# mega_shield3.net
KiCad netlist of a schematic drawn in EAGLE
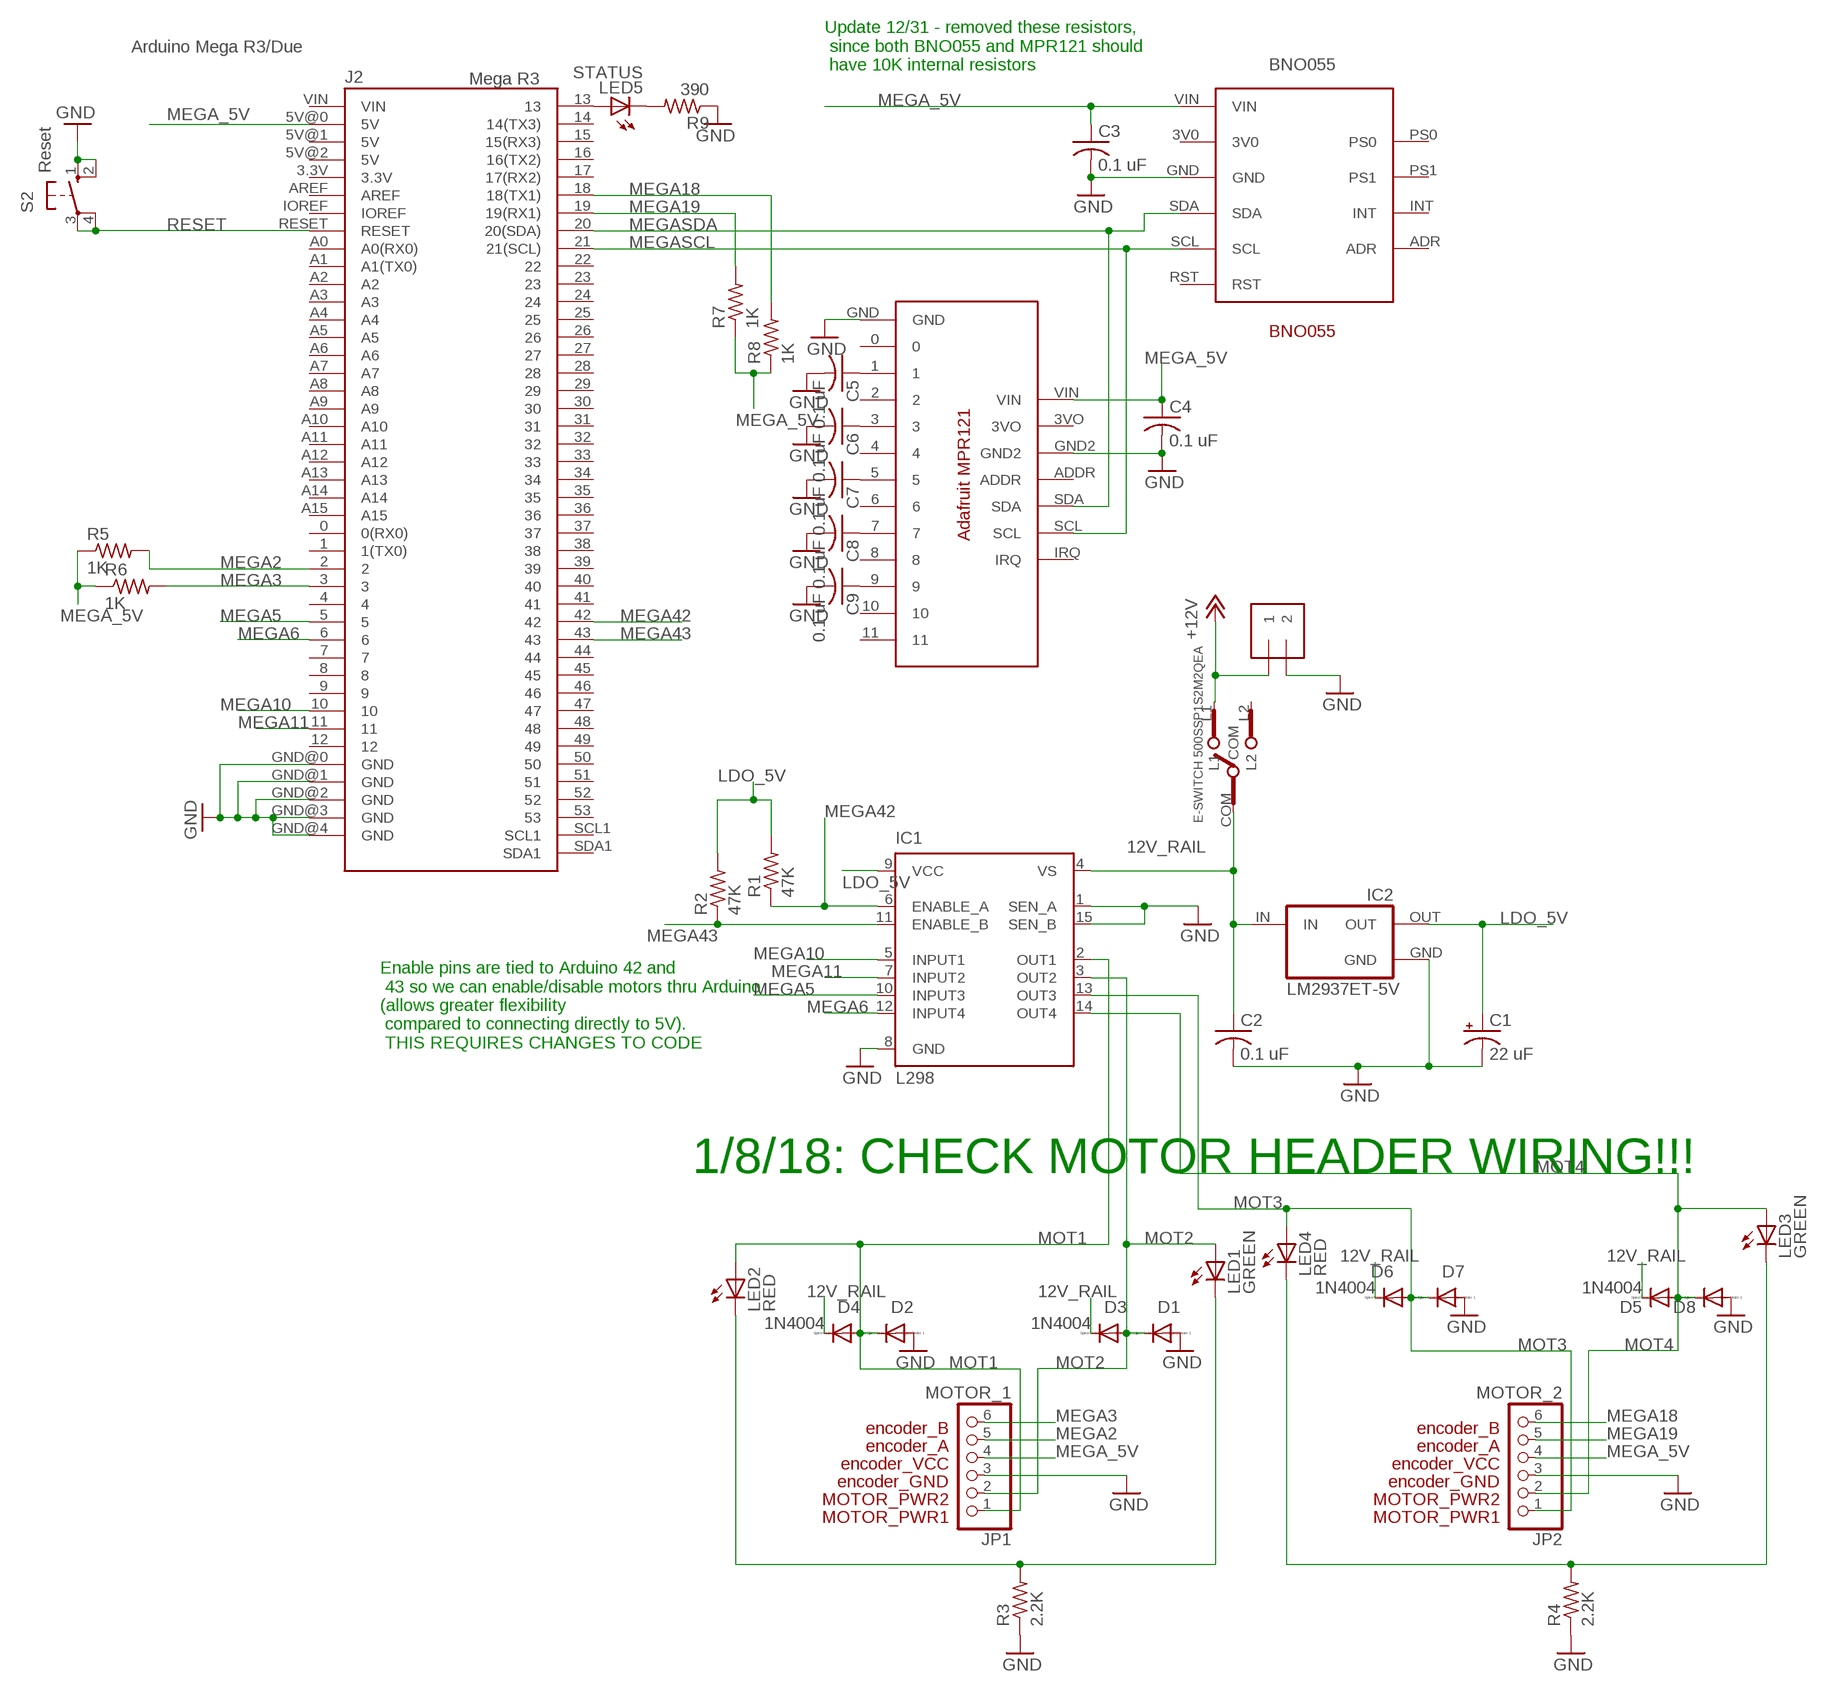
[diagram p0: schematic, sheet 1]

(export (version "E")
  (design (tool "Eeschema 10.0.6"))
  (components
    (comp (ref "12V_IN")
      (value "1X2-3.5MM")
      (footprint "eagle-import:1X2-3.5MM")
      (libsource (lib "eagle-import") (part "1X2-3.5MM"))
    )
    (comp (ref "BNO055")
      (value "BNO055")
      (footprint "eagle-import:BNO055")
      (libsource (lib "eagle-import") (part "BNO055"))
    )
    (comp (ref "C1")
      (value "22 uF")
      (footprint "eagle-import:B45181A")
      (libsource (lib "eagle-import") (part "CPOL-USB45181A"))
    )
    (comp (ref "C2")
      (value "0.1 uF")
      (footprint "eagle-import:C025-050X050")
      (libsource (lib "eagle-import") (part "C-US025-050X050"))
    )
    (comp (ref "C3")
      (value "0.1 uF")
      (footprint "eagle-import:C025-050X050")
      (libsource (lib "eagle-import") (part "C-US025-050X050"))
    )
    (comp (ref "C4")
      (value "0.1 uF")
      (footprint "eagle-import:C025-050X050")
      (libsource (lib "eagle-import") (part "C-US025-050X050"))
    )
    (comp (ref "C5")
      (value "0.1 uF")
      (footprint "eagle-import:C025-050X050")
      (libsource (lib "eagle-import") (part "C-US025-050X050"))
    )
    (comp (ref "C6")
      (value "0.1 uF")
      (footprint "eagle-import:C025-050X050")
      (libsource (lib "eagle-import") (part "C-US025-050X050"))
    )
    (comp (ref "C7")
      (value "0.1 uF")
      (footprint "eagle-import:C025-050X050")
      (libsource (lib "eagle-import") (part "C-US025-050X050"))
    )
    (comp (ref "C8")
      (value "0.1 uF")
      (footprint "eagle-import:C025-050X050")
      (libsource (lib "eagle-import") (part "C-US025-050X050"))
    )
    (comp (ref "C9")
      (value "0.1 uF")
      (footprint "eagle-import:C025-050X050")
      (libsource (lib "eagle-import") (part "C-US025-050X050"))
    )
    (comp (ref "D1")
      (value "1N4004")
      (footprint "eagle-import:DO41-10")
      (libsource (lib "eagle-import") (part "1N4004"))
    )
    (comp (ref "D2")
      (value "1N4004")
      (footprint "eagle-import:DO41-10")
      (libsource (lib "eagle-import") (part "1N4004"))
    )
    (comp (ref "D3")
      (value "1N4004")
      (footprint "eagle-import:DO41-10")
      (libsource (lib "eagle-import") (part "1N4004"))
    )
    (comp (ref "D4")
      (value "1N4004")
      (footprint "eagle-import:DO41-10")
      (libsource (lib "eagle-import") (part "1N4004"))
    )
    (comp (ref "D5")
      (value "1N4004")
      (footprint "eagle-import:DO41-10")
      (libsource (lib "eagle-import") (part "1N4004"))
    )
    (comp (ref "D6")
      (value "1N4004")
      (footprint "eagle-import:DO41-10")
      (libsource (lib "eagle-import") (part "1N4004"))
    )
    (comp (ref "D7")
      (value "1N4004")
      (footprint "eagle-import:DO41-10")
      (libsource (lib "eagle-import") (part "1N4004"))
    )
    (comp (ref "D8")
      (value "1N4004")
      (footprint "eagle-import:DO41-10")
      (libsource (lib "eagle-import") (part "1N4004"))
    )
    (comp (ref "IC1")
      (value "L298")
      (footprint "eagle-import:MULTIWATT-15")
      (fields (field (name "MPN") "L298N"))
      (libsource (lib "eagle-import") (part "L298"))
    )
    (comp (ref "IC2")
      (value "LM2937ET-5V")
      (footprint "eagle-import:TO220(V)")
      (libsource (lib "eagle-import") (part "LM2937ET-5,0"))
    )
    (comp (ref "J2")
      (value "Mega R3")
      (footprint "eagle-import:ARDUINO_MEGA")
      (libsource (lib "eagle-import") (part "ARDUINO-MEGAFULL"))
    )
    (comp (ref "JP1")
      (value "MOTOR_1")
      (footprint "eagle-import:1X06")
      (libsource (lib "eagle-import") (part "PINHD-1X6"))
    )
    (comp (ref "JP2")
      (value "MOTOR_2")
      (footprint "eagle-import:1X06")
      (libsource (lib "eagle-import") (part "PINHD-1X6"))
    )
    (comp (ref "LED1")
      (value "GREEN")
      (footprint "eagle-import:LED3MM")
      (libsource (lib "eagle-import") (part "LED3MM"))
    )
    (comp (ref "LED2")
      (value "RED")
      (footprint "eagle-import:LED3MM")
      (libsource (lib "eagle-import") (part "LED3MM"))
    )
    (comp (ref "LED3")
      (value "GREEN")
      (footprint "eagle-import:LED3MM")
      (libsource (lib "eagle-import") (part "LED3MM"))
    )
    (comp (ref "LED4")
      (value "RED")
      (footprint "eagle-import:LED3MM")
      (libsource (lib "eagle-import") (part "LED3MM"))
    )
    (comp (ref "LED5")
      (value "STATUS")
      (footprint "eagle-import:LED3MM")
      (libsource (lib "eagle-import") (part "LED3MM"))
    )
    (comp (ref "MPR121")
      (value "ADA_MPR121")
      (footprint "eagle-import:ADA_MPR121")
      (libsource (lib "eagle-import") (part "ADA_MPR121"))
    )
    (comp (ref "R1")
      (value "47K")
      (footprint "eagle-import:0207_10")
      (libsource (lib "eagle-import") (part "R-US_0207/10"))
    )
    (comp (ref "R2")
      (value "47K")
      (footprint "eagle-import:0207_10")
      (libsource (lib "eagle-import") (part "R-US_0207/10"))
    )
    (comp (ref "R3")
      (value "2.2K")
      (footprint "eagle-import:0207_10")
      (libsource (lib "eagle-import") (part "R-US_0207/10"))
    )
    (comp (ref "R4")
      (value "2.2K")
      (footprint "eagle-import:0207_10")
      (libsource (lib "eagle-import") (part "R-US_0207/10"))
    )
    (comp (ref "R5")
      (value "1K")
      (footprint "eagle-import:0207_10")
      (libsource (lib "eagle-import") (part "R-US_0207/10"))
    )
    (comp (ref "R6")
      (value "1K")
      (footprint "eagle-import:0207_10")
      (libsource (lib "eagle-import") (part "R-US_0207/10"))
    )
    (comp (ref "R7")
      (value "1K")
      (footprint "eagle-import:0207_10")
      (libsource (lib "eagle-import") (part "R-US_0207/10"))
    )
    (comp (ref "R8")
      (value "1K")
      (footprint "eagle-import:0207_10")
      (libsource (lib "eagle-import") (part "R-US_0207/10"))
    )
    (comp (ref "R9")
      (value "390")
      (footprint "eagle-import:0207_10")
      (libsource (lib "eagle-import") (part "R-US_0207/10"))
    )
    (comp (ref "S2")
      (value "Reset")
      (footprint "eagle-import:B3F-10XX")
      (fields (field (name "MPN") "B3F-1000"))
      (libsource (lib "eagle-import") (part "10-XX"))
    )
    (comp (ref "SLIDE_SW")
      (value "E-SWITCH_500SSP1S2M2QEA")
      (footprint "eagle-import:E-SWITCH_500SSP1S2M2QEA")
      (libsource (lib "eagle-import") (part "E-SWITCH_500SSP1S2M2QEA"))
    )
  )
  (nets
    (net (code "1") (name "+12V") (class "Default")
      (node (ref "12V_IN") (pin "1") (pinfunction "1_1") (pintype "passive"))
      (node (ref "SLIDE_SW") (pin "L1") (pinfunction "L1_L1") (pintype "bidirectional"))
    )
    (net (code "2") (name "/12V_RAIL") (class "Default")
      (node (ref "C2") (pin "1") (pinfunction "1_1") (pintype "passive"))
      (node (ref "D3") (pin "C") (pinfunction "C_C") (pintype "passive"))
      (node (ref "D4") (pin "C") (pinfunction "C_C") (pintype "passive"))
      (node (ref "D5") (pin "C") (pinfunction "C_C") (pintype "passive"))
      (node (ref "D6") (pin "C") (pinfunction "C_C") (pintype "passive"))
      (node (ref "IC1") (pin "4") (pinfunction "VS_4") (pintype "power_in"))
      (node (ref "IC2") (pin "IN") (pinfunction "IN_IN") (pintype "input"))
      (node (ref "SLIDE_SW") (pin "COM") (pinfunction "COM_COM") (pintype "bidirectional"))
    )
    (net (code "3") (name "/LDO_5V") (class "Default")
      (node (ref "C1") (pin "+") (pinfunction "+_+") (pintype "passive"))
      (node (ref "IC1") (pin "9") (pinfunction "VCC_9") (pintype "power_in"))
      (node (ref "IC2") (pin "OUT") (pinfunction "OUT_OUT") (pintype "output"))
      (node (ref "R1") (pin "2") (pinfunction "2_2") (pintype "passive"))
      (node (ref "R2") (pin "2") (pinfunction "2_2") (pintype "passive"))
    )
    (net (code "4") (name "/MEGA2") (class "Default")
      (node (ref "J2") (pin "2") (pinfunction "2_2") (pintype "bidirectional"))
      (node (ref "JP1") (pin "5") (pinfunction "5_5") (pintype "passive"))
      (node (ref "R5") (pin "2") (pinfunction "2_2") (pintype "passive"))
    )
    (net (code "5") (name "/MEGA3") (class "Default")
      (node (ref "J2") (pin "3") (pinfunction "3_3") (pintype "bidirectional"))
      (node (ref "JP1") (pin "6") (pinfunction "6_6") (pintype "passive"))
      (node (ref "R6") (pin "2") (pinfunction "2_2") (pintype "passive"))
    )
    (net (code "6") (name "/MEGA5") (class "Default")
      (node (ref "IC1") (pin "10") (pinfunction "INPUT3_10") (pintype "input"))
      (node (ref "J2") (pin "5") (pinfunction "5_5") (pintype "bidirectional"))
    )
    (net (code "7") (name "/MEGA6") (class "Default")
      (node (ref "IC1") (pin "12") (pinfunction "INPUT4_12") (pintype "input"))
      (node (ref "J2") (pin "6") (pinfunction "6_6") (pintype "bidirectional"))
    )
    (net (code "8") (name "/MEGA10") (class "Default")
      (node (ref "IC1") (pin "5") (pinfunction "INPUT1_5") (pintype "input"))
      (node (ref "J2") (pin "10") (pinfunction "10_10") (pintype "bidirectional"))
    )
    (net (code "9") (name "/MEGA11") (class "Default")
      (node (ref "IC1") (pin "7") (pinfunction "INPUT2_7") (pintype "input"))
      (node (ref "J2") (pin "11") (pinfunction "11_11") (pintype "bidirectional"))
    )
    (net (code "10") (name "/MEGA18") (class "Default")
      (node (ref "J2") (pin "18") (pinfunction "18(TX1)_18") (pintype "bidirectional"))
      (node (ref "JP2") (pin "6") (pinfunction "6_6") (pintype "passive"))
      (node (ref "R8") (pin "2") (pinfunction "2_2") (pintype "passive"))
    )
    (net (code "11") (name "/MEGA19") (class "Default")
      (node (ref "J2") (pin "19") (pinfunction "19(RX1)_19") (pintype "bidirectional"))
      (node (ref "JP2") (pin "5") (pinfunction "5_5") (pintype "passive"))
      (node (ref "R7") (pin "2") (pinfunction "2_2") (pintype "passive"))
    )
    (net (code "12") (name "/MEGA42") (class "Default")
      (node (ref "IC1") (pin "6") (pinfunction "ENABLE_A_6") (pintype "input"))
      (node (ref "J2") (pin "42") (pinfunction "42_42") (pintype "bidirectional"))
      (node (ref "R1") (pin "1") (pinfunction "1_1") (pintype "passive"))
    )
    (net (code "13") (name "/MEGA43") (class "Default")
      (node (ref "IC1") (pin "11") (pinfunction "ENABLE_B_11") (pintype "input"))
      (node (ref "J2") (pin "43") (pinfunction "43_43") (pintype "bidirectional"))
      (node (ref "R2") (pin "1") (pinfunction "1_1") (pintype "passive"))
    )
    (net (code "14") (name "/MEGASCL") (class "Default")
      (node (ref "BNO055") (pin "SCL") (pinfunction "SCL_SCL") (pintype "bidirectional"))
      (node (ref "J2") (pin "21") (pinfunction "21(SCL)_21") (pintype "bidirectional"))
      (node (ref "MPR121") (pin "SCL") (pinfunction "SCL_SCL") (pintype "bidirectional"))
    )
    (net (code "15") (name "/MEGASDA") (class "Default")
      (node (ref "BNO055") (pin "SDA") (pinfunction "SDA_SDA") (pintype "bidirectional"))
      (node (ref "J2") (pin "20") (pinfunction "20(SDA)_20") (pintype "bidirectional"))
      (node (ref "MPR121") (pin "SDA") (pinfunction "SDA_SDA") (pintype "bidirectional"))
    )
    (net (code "16") (name "/MEGA_5V") (class "Default")
      (node (ref "BNO055") (pin "VIN") (pinfunction "VIN_VIN") (pintype "bidirectional"))
      (node (ref "C3") (pin "1") (pinfunction "1_1") (pintype "passive"))
      (node (ref "C4") (pin "1") (pinfunction "1_1") (pintype "passive"))
      (node (ref "J2") (pin "5V@0") (pinfunction "5V_5V@0") (pintype "bidirectional"))
      (node (ref "JP1") (pin "4") (pinfunction "4_4") (pintype "passive"))
      (node (ref "JP2") (pin "4") (pinfunction "4_4") (pintype "passive"))
      (node (ref "MPR121") (pin "VIN") (pinfunction "VIN_VIN") (pintype "bidirectional"))
      (node (ref "R5") (pin "1") (pinfunction "1_1") (pintype "passive"))
      (node (ref "R6") (pin "1") (pinfunction "1_1") (pintype "passive"))
      (node (ref "R7") (pin "1") (pinfunction "1_1") (pintype "passive"))
      (node (ref "R8") (pin "1") (pinfunction "1_1") (pintype "passive"))
    )
    (net (code "17") (name "/MOT1") (class "Default")
      (node (ref "D2") (pin "C") (pinfunction "C_C") (pintype "passive"))
      (node (ref "D4") (pin "A") (pinfunction "A_A") (pintype "passive"))
      (node (ref "IC1") (pin "2") (pinfunction "OUT1_2") (pintype "output"))
      (node (ref "JP1") (pin "1") (pinfunction "1_1") (pintype "passive"))
      (node (ref "LED2") (pin "A") (pinfunction "A_A") (pintype "passive"))
    )
    (net (code "18") (name "/MOT2") (class "Default")
      (node (ref "D1") (pin "C") (pinfunction "C_C") (pintype "passive"))
      (node (ref "D3") (pin "A") (pinfunction "A_A") (pintype "passive"))
      (node (ref "IC1") (pin "3") (pinfunction "OUT2_3") (pintype "output"))
      (node (ref "JP1") (pin "2") (pinfunction "2_2") (pintype "passive"))
      (node (ref "LED1") (pin "A") (pinfunction "A_A") (pintype "passive"))
    )
    (net (code "19") (name "/MOT3") (class "Default")
      (node (ref "D6") (pin "A") (pinfunction "A_A") (pintype "passive"))
      (node (ref "D7") (pin "C") (pinfunction "C_C") (pintype "passive"))
      (node (ref "IC1") (pin "13") (pinfunction "OUT3_13") (pintype "output"))
      (node (ref "JP2") (pin "1") (pinfunction "1_1") (pintype "passive"))
      (node (ref "LED4") (pin "A") (pinfunction "A_A") (pintype "passive"))
    )
    (net (code "20") (name "/MOT4") (class "Default")
      (node (ref "D5") (pin "A") (pinfunction "A_A") (pintype "passive"))
      (node (ref "D8") (pin "C") (pinfunction "C_C") (pintype "passive"))
      (node (ref "IC1") (pin "14") (pinfunction "OUT4_14") (pintype "output"))
      (node (ref "JP2") (pin "2") (pinfunction "2_2") (pintype "passive"))
      (node (ref "LED3") (pin "A") (pinfunction "A_A") (pintype "passive"))
    )
    (net (code "21") (name "/RESET") (class "Default")
      (node (ref "J2") (pin "RESET") (pinfunction "RESET_RESET") (pintype "bidirectional"))
      (node (ref "S2") (pin "3") (pinfunction "P_3") (pintype "passive"))
      (node (ref "S2") (pin "4") (pinfunction "P1_4") (pintype "passive"))
    )
    (net (code "22") (name "GND") (class "Default")
      (node (ref "12V_IN") (pin "2") (pinfunction "2_2") (pintype "passive"))
      (node (ref "BNO055") (pin "GND") (pinfunction "GND_GND") (pintype "bidirectional"))
      (node (ref "C1") (pin "-") (pinfunction "-_-") (pintype "passive"))
      (node (ref "C2") (pin "2") (pinfunction "2_2") (pintype "passive"))
      (node (ref "C3") (pin "2") (pinfunction "2_2") (pintype "passive"))
      (node (ref "C4") (pin "2") (pinfunction "2_2") (pintype "passive"))
      (node (ref "C5") (pin "2") (pinfunction "2_2") (pintype "passive"))
      (node (ref "C6") (pin "2") (pinfunction "2_2") (pintype "passive"))
      (node (ref "C7") (pin "2") (pinfunction "2_2") (pintype "passive"))
      (node (ref "C8") (pin "2") (pinfunction "2_2") (pintype "passive"))
      (node (ref "C9") (pin "2") (pinfunction "2_2") (pintype "passive"))
      (node (ref "D1") (pin "A") (pinfunction "A_A") (pintype "passive"))
      (node (ref "D2") (pin "A") (pinfunction "A_A") (pintype "passive"))
      (node (ref "D7") (pin "A") (pinfunction "A_A") (pintype "passive"))
      (node (ref "D8") (pin "A") (pinfunction "A_A") (pintype "passive"))
      (node (ref "IC1") (pin "1") (pinfunction "SEN_A_1") (pintype "input"))
      (node (ref "IC1") (pin "15") (pinfunction "SEN_B_15") (pintype "input"))
      (node (ref "IC1") (pin "8") (pinfunction "GND_8") (pintype "power_in"))
      (node (ref "IC2") (pin "GND") (pinfunction "GND_GND") (pintype "power_in"))
      (node (ref "J2") (pin "GND@0") (pinfunction "GND_GND@0") (pintype "bidirectional"))
      (node (ref "J2") (pin "GND@1") (pinfunction "GND_GND@1") (pintype "bidirectional"))
      (node (ref "J2") (pin "GND@2") (pinfunction "GND_GND@2") (pintype "bidirectional"))
      (node (ref "J2") (pin "GND@3") (pinfunction "GND_GND@3") (pintype "bidirectional"))
      (node (ref "J2") (pin "GND@4") (pinfunction "GND_GND@4") (pintype "bidirectional"))
      (node (ref "JP1") (pin "3") (pinfunction "3_3") (pintype "passive"))
      (node (ref "JP2") (pin "3") (pinfunction "3_3") (pintype "passive"))
      (node (ref "MPR121") (pin "GND") (pinfunction "GND_GND") (pintype "bidirectional"))
      (node (ref "MPR121") (pin "GND2") (pinfunction "GND2_GND2") (pintype "bidirectional"))
      (node (ref "R3") (pin "1") (pinfunction "1_1") (pintype "passive"))
      (node (ref "R4") (pin "1") (pinfunction "1_1") (pintype "passive"))
      (node (ref "R9") (pin "1") (pinfunction "1_1") (pintype "passive"))
      (node (ref "S2") (pin "1") (pinfunction "S_1") (pintype "passive"))
      (node (ref "S2") (pin "2") (pinfunction "S1_2") (pintype "passive"))
    )
    (net (code "23") (name "Net-(C5-Pad1)") (class "Default")
      (node (ref "C5") (pin "1") (pinfunction "1_1") (pintype "passive"))
      (node (ref "MPR121") (pin "1") (pinfunction "1_1") (pintype "bidirectional"))
    )
    (net (code "24") (name "Net-(C6-Pad1)") (class "Default")
      (node (ref "C6") (pin "1") (pinfunction "1_1") (pintype "passive"))
      (node (ref "MPR121") (pin "3") (pinfunction "3_3") (pintype "bidirectional"))
    )
    (net (code "25") (name "Net-(C7-Pad1)") (class "Default")
      (node (ref "C7") (pin "1") (pinfunction "1_1") (pintype "passive"))
      (node (ref "MPR121") (pin "5") (pinfunction "5_5") (pintype "bidirectional"))
    )
    (net (code "26") (name "Net-(C8-Pad1)") (class "Default")
      (node (ref "C8") (pin "1") (pinfunction "1_1") (pintype "passive"))
      (node (ref "MPR121") (pin "7") (pinfunction "7_7") (pintype "bidirectional"))
    )
    (net (code "27") (name "Net-(C9-Pad1)") (class "Default")
      (node (ref "C9") (pin "1") (pinfunction "1_1") (pintype "passive"))
      (node (ref "MPR121") (pin "9") (pinfunction "9_9") (pintype "bidirectional"))
    )
    (net (code "28") (name "Net-(J2-Pad13)") (class "Default")
      (node (ref "J2") (pin "13") (pinfunction "13_13") (pintype "bidirectional"))
      (node (ref "LED5") (pin "A") (pinfunction "A_A") (pintype "passive"))
    )
    (net (code "29") (name "Net-(LED1-C)") (class "Default")
      (node (ref "LED1") (pin "K") (pinfunction "C_K") (pintype "passive"))
      (node (ref "LED2") (pin "K") (pinfunction "C_K") (pintype "passive"))
      (node (ref "R3") (pin "2") (pinfunction "2_2") (pintype "passive"))
    )
    (net (code "30") (name "Net-(LED3-C)") (class "Default")
      (node (ref "LED3") (pin "K") (pinfunction "C_K") (pintype "passive"))
      (node (ref "LED4") (pin "K") (pinfunction "C_K") (pintype "passive"))
      (node (ref "R4") (pin "2") (pinfunction "2_2") (pintype "passive"))
    )
    (net (code "31") (name "Net-(LED5-C)") (class "Default")
      (node (ref "LED5") (pin "K") (pinfunction "C_K") (pintype "passive"))
      (node (ref "R9") (pin "2") (pinfunction "2_2") (pintype "passive"))
    )
    (net (code "32") (name "unconnected-(BNO055-Pad3V0)") (class "Default")
      (node (ref "BNO055") (pin "3V0") (pinfunction "3V0_3V0") (pintype "bidirectional"))
    )
    (net (code "33") (name "unconnected-(BNO055-PadADR)") (class "Default")
      (node (ref "BNO055") (pin "ADR") (pinfunction "ADR_ADR") (pintype "bidirectional"))
    )
    (net (code "34") (name "unconnected-(BNO055-PadINT)") (class "Default")
      (node (ref "BNO055") (pin "INT") (pinfunction "INT_INT") (pintype "bidirectional"))
    )
    (net (code "35") (name "unconnected-(BNO055-PadPS0)") (class "Default")
      (node (ref "BNO055") (pin "PS0") (pinfunction "PS0_PS0") (pintype "bidirectional"))
    )
    (net (code "36") (name "unconnected-(BNO055-PadPS1)") (class "Default")
      (node (ref "BNO055") (pin "PS1") (pinfunction "PS1_PS1") (pintype "bidirectional"))
    )
    (net (code "37") (name "unconnected-(BNO055-PadRST)") (class "Default")
      (node (ref "BNO055") (pin "RST") (pinfunction "RST_RST") (pintype "bidirectional"))
    )
    (net (code "38") (name "unconnected-(J2-0(RX0)-Pad0)") (class "Default")
      (node (ref "J2") (pin "0") (pinfunction "0(RX0)_0") (pintype "bidirectional"))
    )
    (net (code "39") (name "unconnected-(J2-1(TX0)-Pad1)") (class "Default")
      (node (ref "J2") (pin "1") (pinfunction "1(TX0)_1") (pintype "bidirectional"))
    )
    (net (code "40") (name "unconnected-(J2-5V-Pad5V@1)") (class "Default")
      (node (ref "J2") (pin "5V@1") (pinfunction "5V_5V@1") (pintype "bidirectional"))
    )
    (net (code "41") (name "unconnected-(J2-5V-Pad5V@2)") (class "Default")
      (node (ref "J2") (pin "5V@2") (pinfunction "5V_5V@2") (pintype "bidirectional"))
    )
    (net (code "42") (name "unconnected-(J2-14(TX3)-Pad14)") (class "Default")
      (node (ref "J2") (pin "14") (pinfunction "14(TX3)_14") (pintype "bidirectional"))
    )
    (net (code "43") (name "unconnected-(J2-15(RX3)-Pad15)") (class "Default")
      (node (ref "J2") (pin "15") (pinfunction "15(RX3)_15") (pintype "bidirectional"))
    )
    (net (code "44") (name "unconnected-(J2-16(TX2)-Pad16)") (class "Default")
      (node (ref "J2") (pin "16") (pinfunction "16(TX2)_16") (pintype "bidirectional"))
    )
    (net (code "45") (name "unconnected-(J2-17(RX2)-Pad17)") (class "Default")
      (node (ref "J2") (pin "17") (pinfunction "17(RX2)_17") (pintype "bidirectional"))
    )
    (net (code "46") (name "unconnected-(J2-A0(RX0)-PadA0)") (class "Default")
      (node (ref "J2") (pin "A0") (pinfunction "A0(RX0)_A0") (pintype "bidirectional"))
    )
    (net (code "47") (name "unconnected-(J2-A1(TX0)-PadA1)") (class "Default")
      (node (ref "J2") (pin "A1") (pinfunction "A1(TX0)_A1") (pintype "bidirectional"))
    )
    (net (code "48") (name "unconnected-(J2-Pad3.3V)") (class "Default")
      (node (ref "J2") (pin "3.3V") (pinfunction "3.3V_3.3V") (pintype "bidirectional"))
    )
    (net (code "49") (name "unconnected-(J2-Pad4)") (class "Default")
      (node (ref "J2") (pin "4") (pinfunction "4_4") (pintype "bidirectional"))
    )
    (net (code "50") (name "unconnected-(J2-Pad7)") (class "Default")
      (node (ref "J2") (pin "7") (pinfunction "7_7") (pintype "bidirectional"))
    )
    (net (code "51") (name "unconnected-(J2-Pad8)") (class "Default")
      (node (ref "J2") (pin "8") (pinfunction "8_8") (pintype "bidirectional"))
    )
    (net (code "52") (name "unconnected-(J2-Pad9)") (class "Default")
      (node (ref "J2") (pin "9") (pinfunction "9_9") (pintype "bidirectional"))
    )
    (net (code "53") (name "unconnected-(J2-Pad12)") (class "Default")
      (node (ref "J2") (pin "12") (pinfunction "12_12") (pintype "bidirectional"))
    )
    (net (code "54") (name "unconnected-(J2-Pad22)") (class "Default")
      (node (ref "J2") (pin "22") (pinfunction "22_22") (pintype "bidirectional"))
    )
    (net (code "55") (name "unconnected-(J2-Pad23)") (class "Default")
      (node (ref "J2") (pin "23") (pinfunction "23_23") (pintype "bidirectional"))
    )
    (net (code "56") (name "unconnected-(J2-Pad24)") (class "Default")
      (node (ref "J2") (pin "24") (pinfunction "24_24") (pintype "bidirectional"))
    )
    (net (code "57") (name "unconnected-(J2-Pad25)") (class "Default")
      (node (ref "J2") (pin "25") (pinfunction "25_25") (pintype "bidirectional"))
    )
    (net (code "58") (name "unconnected-(J2-Pad26)") (class "Default")
      (node (ref "J2") (pin "26") (pinfunction "26_26") (pintype "bidirectional"))
    )
    (net (code "59") (name "unconnected-(J2-Pad27)") (class "Default")
      (node (ref "J2") (pin "27") (pinfunction "27_27") (pintype "bidirectional"))
    )
    (net (code "60") (name "unconnected-(J2-Pad28)") (class "Default")
      (node (ref "J2") (pin "28") (pinfunction "28_28") (pintype "bidirectional"))
    )
    (net (code "61") (name "unconnected-(J2-Pad29)") (class "Default")
      (node (ref "J2") (pin "29") (pinfunction "29_29") (pintype "bidirectional"))
    )
    (net (code "62") (name "unconnected-(J2-Pad30)") (class "Default")
      (node (ref "J2") (pin "30") (pinfunction "30_30") (pintype "bidirectional"))
    )
    (net (code "63") (name "unconnected-(J2-Pad31)") (class "Default")
      (node (ref "J2") (pin "31") (pinfunction "31_31") (pintype "bidirectional"))
    )
    (net (code "64") (name "unconnected-(J2-Pad32)") (class "Default")
      (node (ref "J2") (pin "32") (pinfunction "32_32") (pintype "bidirectional"))
    )
    (net (code "65") (name "unconnected-(J2-Pad33)") (class "Default")
      (node (ref "J2") (pin "33") (pinfunction "33_33") (pintype "bidirectional"))
    )
    (net (code "66") (name "unconnected-(J2-Pad34)") (class "Default")
      (node (ref "J2") (pin "34") (pinfunction "34_34") (pintype "bidirectional"))
    )
    (net (code "67") (name "unconnected-(J2-Pad35)") (class "Default")
      (node (ref "J2") (pin "35") (pinfunction "35_35") (pintype "bidirectional"))
    )
    (net (code "68") (name "unconnected-(J2-Pad36)") (class "Default")
      (node (ref "J2") (pin "36") (pinfunction "36_36") (pintype "bidirectional"))
    )
    (net (code "69") (name "unconnected-(J2-Pad37)") (class "Default")
      (node (ref "J2") (pin "37") (pinfunction "37_37") (pintype "bidirectional"))
    )
    (net (code "70") (name "unconnected-(J2-Pad38)") (class "Default")
      (node (ref "J2") (pin "38") (pinfunction "38_38") (pintype "bidirectional"))
    )
    (net (code "71") (name "unconnected-(J2-Pad39)") (class "Default")
      (node (ref "J2") (pin "39") (pinfunction "39_39") (pintype "bidirectional"))
    )
    (net (code "72") (name "unconnected-(J2-Pad40)") (class "Default")
      (node (ref "J2") (pin "40") (pinfunction "40_40") (pintype "bidirectional"))
    )
    (net (code "73") (name "unconnected-(J2-Pad41)") (class "Default")
      (node (ref "J2") (pin "41") (pinfunction "41_41") (pintype "bidirectional"))
    )
    (net (code "74") (name "unconnected-(J2-Pad44)") (class "Default")
      (node (ref "J2") (pin "44") (pinfunction "44_44") (pintype "bidirectional"))
    )
    (net (code "75") (name "unconnected-(J2-Pad45)") (class "Default")
      (node (ref "J2") (pin "45") (pinfunction "45_45") (pintype "bidirectional"))
    )
    (net (code "76") (name "unconnected-(J2-Pad46)") (class "Default")
      (node (ref "J2") (pin "46") (pinfunction "46_46") (pintype "bidirectional"))
    )
    (net (code "77") (name "unconnected-(J2-Pad47)") (class "Default")
      (node (ref "J2") (pin "47") (pinfunction "47_47") (pintype "bidirectional"))
    )
    (net (code "78") (name "unconnected-(J2-Pad48)") (class "Default")
      (node (ref "J2") (pin "48") (pinfunction "48_48") (pintype "bidirectional"))
    )
    (net (code "79") (name "unconnected-(J2-Pad49)") (class "Default")
      (node (ref "J2") (pin "49") (pinfunction "49_49") (pintype "bidirectional"))
    )
    (net (code "80") (name "unconnected-(J2-Pad50)") (class "Default")
      (node (ref "J2") (pin "50") (pinfunction "50_50") (pintype "bidirectional"))
    )
    (net (code "81") (name "unconnected-(J2-Pad51)") (class "Default")
      (node (ref "J2") (pin "51") (pinfunction "51_51") (pintype "bidirectional"))
    )
    (net (code "82") (name "unconnected-(J2-Pad52)") (class "Default")
      (node (ref "J2") (pin "52") (pinfunction "52_52") (pintype "bidirectional"))
    )
    (net (code "83") (name "unconnected-(J2-Pad53)") (class "Default")
      (node (ref "J2") (pin "53") (pinfunction "53_53") (pintype "bidirectional"))
    )
    (net (code "84") (name "unconnected-(J2-PadA2)") (class "Default")
      (node (ref "J2") (pin "A2") (pinfunction "A2_A2") (pintype "bidirectional"))
    )
    (net (code "85") (name "unconnected-(J2-PadA3)") (class "Default")
      (node (ref "J2") (pin "A3") (pinfunction "A3_A3") (pintype "bidirectional"))
    )
    (net (code "86") (name "unconnected-(J2-PadA4)") (class "Default")
      (node (ref "J2") (pin "A4") (pinfunction "A4_A4") (pintype "bidirectional"))
    )
    (net (code "87") (name "unconnected-(J2-PadA5)") (class "Default")
      (node (ref "J2") (pin "A5") (pinfunction "A5_A5") (pintype "bidirectional"))
    )
    (net (code "88") (name "unconnected-(J2-PadA6)") (class "Default")
      (node (ref "J2") (pin "A6") (pinfunction "A6_A6") (pintype "bidirectional"))
    )
    (net (code "89") (name "unconnected-(J2-PadA7)") (class "Default")
      (node (ref "J2") (pin "A7") (pinfunction "A7_A7") (pintype "bidirectional"))
    )
    (net (code "90") (name "unconnected-(J2-PadA8)") (class "Default")
      (node (ref "J2") (pin "A8") (pinfunction "A8_A8") (pintype "bidirectional"))
    )
    (net (code "91") (name "unconnected-(J2-PadA9)") (class "Default")
      (node (ref "J2") (pin "A9") (pinfunction "A9_A9") (pintype "bidirectional"))
    )
    (net (code "92") (name "unconnected-(J2-PadA10)") (class "Default")
      (node (ref "J2") (pin "A10") (pinfunction "A10_A10") (pintype "bidirectional"))
    )
    (net (code "93") (name "unconnected-(J2-PadA11)") (class "Default")
      (node (ref "J2") (pin "A11") (pinfunction "A11_A11") (pintype "bidirectional"))
    )
    (net (code "94") (name "unconnected-(J2-PadA12)") (class "Default")
      (node (ref "J2") (pin "A12") (pinfunction "A12_A12") (pintype "bidirectional"))
    )
    (net (code "95") (name "unconnected-(J2-PadA13)") (class "Default")
      (node (ref "J2") (pin "A13") (pinfunction "A13_A13") (pintype "bidirectional"))
    )
    (net (code "96") (name "unconnected-(J2-PadA14)") (class "Default")
      (node (ref "J2") (pin "A14") (pinfunction "A14_A14") (pintype "bidirectional"))
    )
    (net (code "97") (name "unconnected-(J2-PadA15)") (class "Default")
      (node (ref "J2") (pin "A15") (pinfunction "A15_A15") (pintype "bidirectional"))
    )
    (net (code "98") (name "unconnected-(J2-PadAREF)") (class "Default")
      (node (ref "J2") (pin "AREF") (pinfunction "AREF_AREF") (pintype "bidirectional"))
    )
    (net (code "99") (name "unconnected-(J2-PadIOREF)") (class "Default")
      (node (ref "J2") (pin "IOREF") (pinfunction "IOREF_IOREF") (pintype "bidirectional"))
    )
    (net (code "100") (name "unconnected-(J2-PadSCL1)") (class "Default")
      (node (ref "J2") (pin "SCL1") (pinfunction "SCL1_SCL1") (pintype "bidirectional"))
    )
    (net (code "101") (name "unconnected-(J2-PadSDA1)") (class "Default")
      (node (ref "J2") (pin "SDA1") (pinfunction "SDA1_SDA1") (pintype "bidirectional"))
    )
    (net (code "102") (name "unconnected-(J2-PadVIN)") (class "Default")
      (node (ref "J2") (pin "VIN") (pinfunction "VIN_VIN") (pintype "bidirectional"))
    )
    (net (code "103") (name "unconnected-(MPR121-Pad0)") (class "Default")
      (node (ref "MPR121") (pin "0") (pinfunction "0_0") (pintype "bidirectional"))
    )
    (net (code "104") (name "unconnected-(MPR121-Pad2)") (class "Default")
      (node (ref "MPR121") (pin "2") (pinfunction "2_2") (pintype "bidirectional"))
    )
    (net (code "105") (name "unconnected-(MPR121-Pad3VO)") (class "Default")
      (node (ref "MPR121") (pin "3VO") (pinfunction "3VO_3VO") (pintype "bidirectional"))
    )
    (net (code "106") (name "unconnected-(MPR121-Pad4)") (class "Default")
      (node (ref "MPR121") (pin "4") (pinfunction "4_4") (pintype "bidirectional"))
    )
    (net (code "107") (name "unconnected-(MPR121-Pad6)") (class "Default")
      (node (ref "MPR121") (pin "6") (pinfunction "6_6") (pintype "bidirectional"))
    )
    (net (code "108") (name "unconnected-(MPR121-Pad8)") (class "Default")
      (node (ref "MPR121") (pin "8") (pinfunction "8_8") (pintype "bidirectional"))
    )
    (net (code "109") (name "unconnected-(MPR121-Pad10)") (class "Default")
      (node (ref "MPR121") (pin "10") (pinfunction "10_10") (pintype "bidirectional"))
    )
    (net (code "110") (name "unconnected-(MPR121-Pad11)") (class "Default")
      (node (ref "MPR121") (pin "11") (pinfunction "11_11") (pintype "bidirectional"))
    )
    (net (code "111") (name "unconnected-(MPR121-PadADDR)") (class "Default")
      (node (ref "MPR121") (pin "ADDR") (pinfunction "ADDR_ADDR") (pintype "bidirectional"))
    )
    (net (code "112") (name "unconnected-(MPR121-PadIRQ)") (class "Default")
      (node (ref "MPR121") (pin "IRQ") (pinfunction "IRQ_IRQ") (pintype "bidirectional"))
    )
    (net (code "113") (name "unconnected-(SLIDE_SW-PadL2)") (class "Default")
      (node (ref "SLIDE_SW") (pin "L2") (pinfunction "L2_L2") (pintype "bidirectional"))
    )
  )
)
